# esp8266.net
KiCad netlist of a schematic drawn in EAGLE
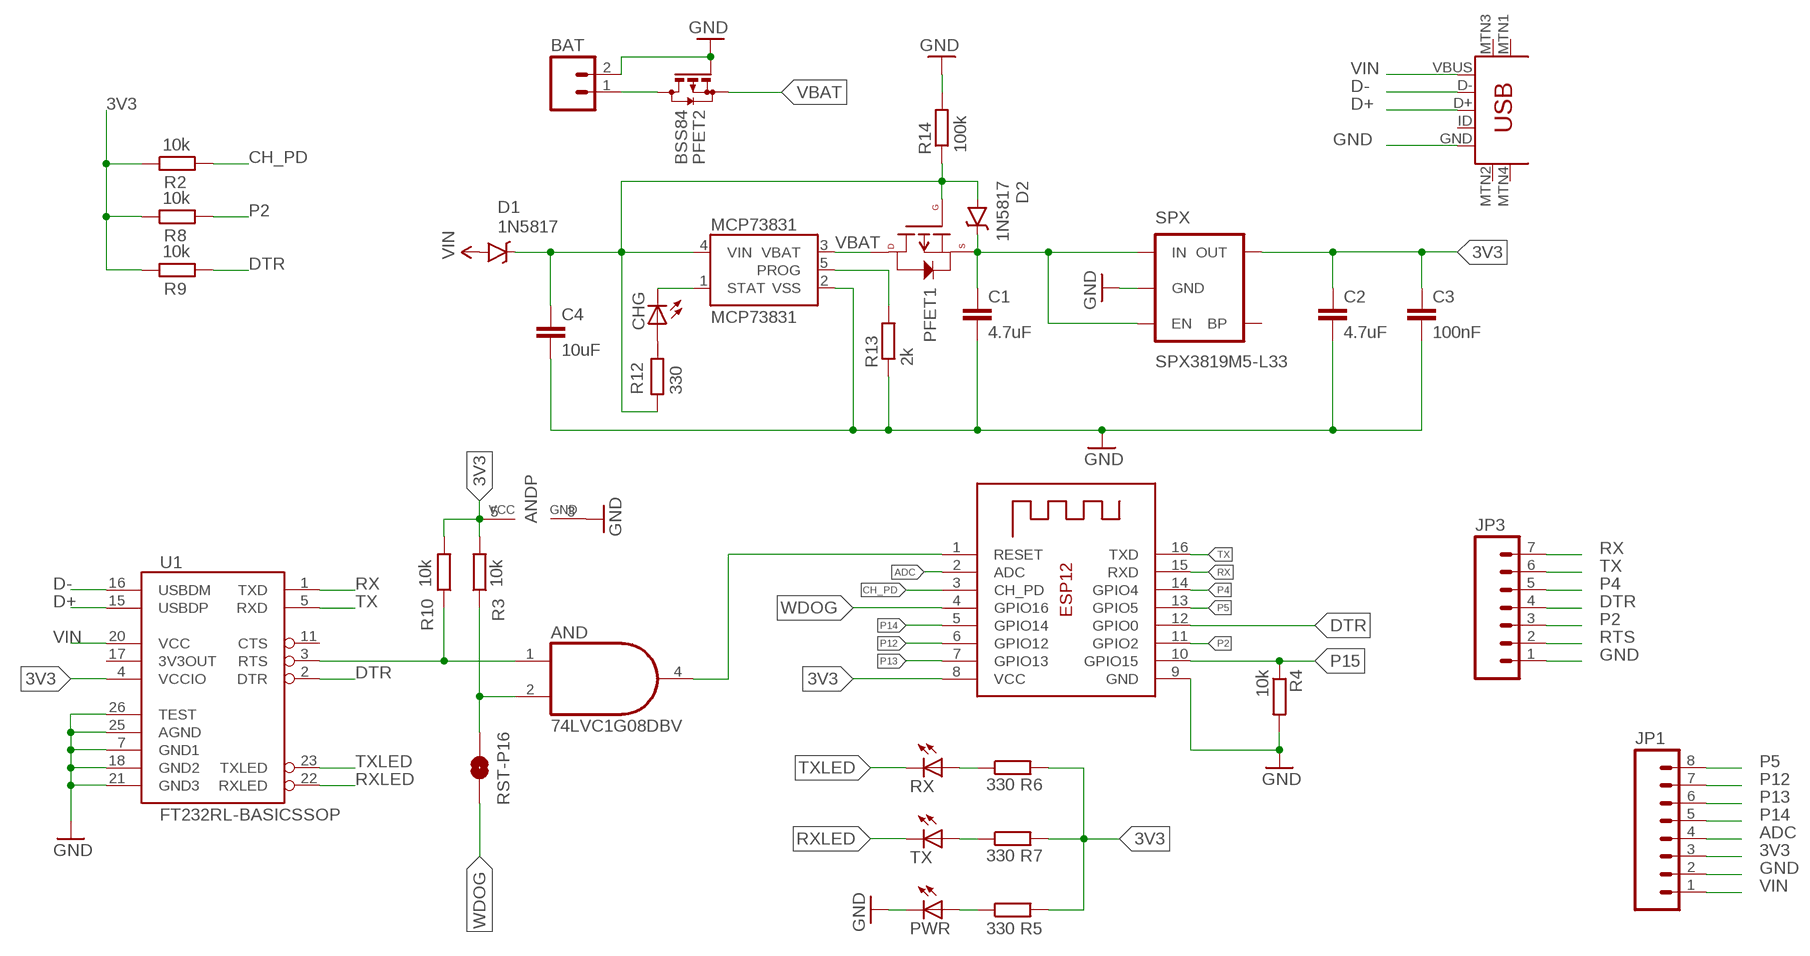
[diagram p0: schematic, sheet 1]

(export (version "E")
  (design (tool "Eeschema 10.0.6"))
  (components
    (comp (ref "AND")
      (value "74LVC1G08DBV")
      (footprint "eagle-import:SOT23-5")
      (libsource (lib "eagle-import") (part "741G08DBVLVC"))
    )
    (comp (ref "BAT")
      (value "M02LOCK")
      (footprint "eagle-import:1X02_LOCK")
      (libsource (lib "eagle-import") (part "M02LOCK"))
    )
    (comp (ref "C1")
      (value "4.7uF")
      (footprint "eagle-import:C0805")
      (libsource (lib "eagle-import") (part "C-EUC0805"))
    )
    (comp (ref "C2")
      (value "4.7uF")
      (footprint "eagle-import:C0805")
      (libsource (lib "eagle-import") (part "C-EUC0805"))
    )
    (comp (ref "C3")
      (value "100nF")
      (footprint "eagle-import:C0805")
      (libsource (lib "eagle-import") (part "C-EUC0805"))
    )
    (comp (ref "C4")
      (value "10uF")
      (footprint "eagle-import:C0805")
      (libsource (lib "eagle-import") (part "C-EUC0805"))
    )
    (comp (ref "CHG")
      (value "LEDCHIPLED_0805")
      (footprint "eagle-import:CHIPLED_0805")
      (libsource (lib "eagle-import") (part "LEDCHIPLED_0805"))
    )
    (comp (ref "D1")
      (value "1N5817")
      (footprint "eagle-import:SMA-DIODE")
      (libsource (lib "eagle-import") (part "DIODE-SCHOTTKY-MBRA140"))
    )
    (comp (ref "D2")
      (value "1N5817")
      (footprint "eagle-import:SMA-DIODE")
      (libsource (lib "eagle-import") (part "DIODE-SCHOTTKY-MBRA140"))
    )
    (comp (ref "ESP8266-07/12")
      (value "ESP-12")
      (footprint "eagle-import:ESP-12")
      (libsource (lib "eagle-import") (part "ESP-12"))
    )
    (comp (ref "JP1")
      (value "M08LOCK")
      (footprint "eagle-import:1X08_LOCK")
      (libsource (lib "eagle-import") (part "M08LOCK"))
    )
    (comp (ref "JP3")
      (value "M07LOCK")
      (footprint "eagle-import:1X07_LOCK")
      (libsource (lib "eagle-import") (part "M07LOCK"))
    )
    (comp (ref "MCP73831")
      (value "MCP73831")
      (footprint "eagle-import:SOT23-5")
      (libsource (lib "eagle-import") (part "MCP73831"))
    )
    (comp (ref "MINIUSB")
      (value "USB-MINIB-5PIN")
      (footprint "eagle-import:USB-MINIB")
      (libsource (lib "eagle-import") (part "USB-MINIB-5PIN"))
    )
    (comp (ref "PFET1")
      (value "P-CHANNEL-MOSFET")
      (footprint "eagle-import:SOT23-3")
      (libsource (lib "eagle-import") (part "P-CHANNEL-MOSFET"))
    )
    (comp (ref "PFET2")
      (value "BSS84")
      (footprint "eagle-import:SOT23")
      (libsource (lib "eagle-import") (part "BSS84"))
    )
    (comp (ref "PWR")
      (value "LEDCHIPLED_0805")
      (footprint "eagle-import:CHIPLED_0805")
      (libsource (lib "eagle-import") (part "LEDCHIPLED_0805"))
    )
    (comp (ref "R2")
      (value "10k")
      (footprint "eagle-import:R0805")
      (libsource (lib "eagle-import") (part "R-EU_R0805"))
    )
    (comp (ref "R3")
      (value "10k")
      (footprint "eagle-import:R0805")
      (libsource (lib "eagle-import") (part "R-EU_R0805"))
    )
    (comp (ref "R4")
      (value "10k")
      (footprint "eagle-import:R0805")
      (libsource (lib "eagle-import") (part "R-EU_R0805"))
    )
    (comp (ref "R5")
      (value "330")
      (footprint "eagle-import:R0805")
      (libsource (lib "eagle-import") (part "R-EU_R0805"))
    )
    (comp (ref "R6")
      (value "330")
      (footprint "eagle-import:R0805")
      (libsource (lib "eagle-import") (part "R-EU_R0805"))
    )
    (comp (ref "R7")
      (value "330")
      (footprint "eagle-import:R0805")
      (libsource (lib "eagle-import") (part "R-EU_R0805"))
    )
    (comp (ref "R8")
      (value "10k")
      (footprint "eagle-import:R0805")
      (libsource (lib "eagle-import") (part "R-EU_R0805"))
    )
    (comp (ref "R9")
      (value "10k")
      (footprint "eagle-import:R0805")
      (libsource (lib "eagle-import") (part "R-EU_R0805"))
    )
    (comp (ref "R10")
      (value "10k")
      (footprint "eagle-import:R0805")
      (libsource (lib "eagle-import") (part "R-EU_R0805"))
    )
    (comp (ref "R12")
      (value "330")
      (footprint "eagle-import:R0805")
      (libsource (lib "eagle-import") (part "R-EU_R0805"))
    )
    (comp (ref "R13")
      (value "2k")
      (footprint "eagle-import:R0805")
      (libsource (lib "eagle-import") (part "R-EU_R0805"))
    )
    (comp (ref "R14")
      (value "100k")
      (footprint "eagle-import:R0805")
      (libsource (lib "eagle-import") (part "R-EU_R0805"))
    )
    (comp (ref "RST-P16")
      (value "SOLDERJUMPERNO")
      (footprint "eagle-import:SJ_2S-NO")
      (libsource (lib "eagle-import") (part "SOLDERJUMPERNO"))
    )
    (comp (ref "RX")
      (value "LEDCHIPLED_0805")
      (footprint "eagle-import:CHIPLED_0805")
      (libsource (lib "eagle-import") (part "LEDCHIPLED_0805"))
    )
    (comp (ref "SPX")
      (value "SPX3819M5-L33")
      (footprint "eagle-import:SOT23-5")
      (libsource (lib "eagle-import") (part "V_REG_LDOSMD"))
    )
    (comp (ref "TX")
      (value "LEDCHIPLED_0805")
      (footprint "eagle-import:CHIPLED_0805")
      (libsource (lib "eagle-import") (part "LEDCHIPLED_0805"))
    )
    (comp (ref "U1")
      (value "FT232RL-BASICSSOP")
      (footprint "eagle-import:SSOP28DB")
      (libsource (lib "eagle-import") (part "FT232RL-BASICSSOP"))
    )
  )
  (nets
    (net (code "1") (name "/D+") (class "Default")
      (node (ref "MINIUSB") (pin "D+") (pinfunction "D+_D+") (pintype "bidirectional"))
      (node (ref "U1") (pin "15") (pinfunction "USBDP_15") (pintype "bidirectional"))
    )
    (net (code "2") (name "/D-") (class "Default")
      (node (ref "MINIUSB") (pin "D-") (pinfunction "D-_D-") (pintype "bidirectional"))
      (node (ref "U1") (pin "16") (pinfunction "USBDM_16") (pintype "bidirectional"))
    )
    (net (code "3") (name "/RTS") (class "Default")
      (node (ref "AND") (pin "4") (pinfunction "O_4") (pintype "output"))
      (node (ref "ESP8266-07/12") (pin "1") (pinfunction "RESET_1") (pintype "input"))
      (node (ref "JP3") (pin "2") (pinfunction "2_2") (pintype "passive"))
    )
    (net (code "4") (name "3V3") (class "Default")
      (node (ref "AND") (pin "5") (pinfunction "VCC_5") (pintype "power_in"))
      (node (ref "C2") (pin "1") (pinfunction "1_1") (pintype "passive"))
      (node (ref "C3") (pin "1") (pinfunction "1_1") (pintype "passive"))
      (node (ref "ESP8266-07/12") (pin "8") (pinfunction "VCC_8") (pintype "power_in"))
      (node (ref "JP1") (pin "3") (pinfunction "3_3") (pintype "passive"))
      (node (ref "R10") (pin "2") (pinfunction "2_2") (pintype "passive"))
      (node (ref "R2") (pin "1") (pinfunction "1_1") (pintype "passive"))
      (node (ref "R3") (pin "2") (pinfunction "2_2") (pintype "passive"))
      (node (ref "R5") (pin "2") (pinfunction "2_2") (pintype "passive"))
      (node (ref "R6") (pin "2") (pinfunction "2_2") (pintype "passive"))
      (node (ref "R7") (pin "2") (pinfunction "2_2") (pintype "passive"))
      (node (ref "R8") (pin "1") (pinfunction "1_1") (pintype "passive"))
      (node (ref "R9") (pin "1") (pinfunction "1_1") (pintype "passive"))
      (node (ref "SPX") (pin "5") (pinfunction "OUT_5") (pintype "passive"))
      (node (ref "U1") (pin "4") (pinfunction "VCCIO_4") (pintype "power_in"))
    )
    (net (code "5") (name "ADC") (class "Default")
      (node (ref "ESP8266-07/12") (pin "2") (pinfunction "ADC_2") (pintype "passive"))
      (node (ref "JP1") (pin "4") (pinfunction "4_4") (pintype "passive"))
    )
    (net (code "6") (name "CH_PD") (class "Default")
      (node (ref "ESP8266-07/12") (pin "3") (pinfunction "CH_PD_3") (pintype "input"))
      (node (ref "R2") (pin "2") (pinfunction "2_2") (pintype "passive"))
    )
    (net (code "7") (name "DTR") (class "Default")
      (node (ref "ESP8266-07/12") (pin "12") (pinfunction "GPIO0_12") (pintype "bidirectional"))
      (node (ref "JP3") (pin "4") (pinfunction "4_4") (pintype "passive"))
      (node (ref "R9") (pin "2") (pinfunction "2_2") (pintype "passive"))
      (node (ref "U1") (pin "2") (pinfunction "DTR_2") (pintype "bidirectional"))
    )
    (net (code "8") (name "GND") (class "Default")
      (node (ref "AND") (pin "3") (pinfunction "GND_3") (pintype "power_in"))
      (node (ref "BAT") (pin "2") (pinfunction "2_2") (pintype "passive"))
      (node (ref "C1") (pin "2") (pinfunction "2_2") (pintype "passive"))
      (node (ref "C2") (pin "2") (pinfunction "2_2") (pintype "passive"))
      (node (ref "C3") (pin "2") (pinfunction "2_2") (pintype "passive"))
      (node (ref "C4") (pin "2") (pinfunction "2_2") (pintype "passive"))
      (node (ref "ESP8266-07/12") (pin "9") (pinfunction "GND_9") (pintype "power_in"))
      (node (ref "JP1") (pin "2") (pinfunction "2_2") (pintype "passive"))
      (node (ref "JP3") (pin "1") (pinfunction "1_1") (pintype "passive"))
      (node (ref "MCP73831") (pin "2") (pinfunction "VSS_2") (pintype "power_in"))
      (node (ref "MINIUSB") (pin "GND") (pinfunction "GND_GND") (pintype "bidirectional"))
      (node (ref "PFET2") (pin "1") (pinfunction "G_1") (pintype "passive"))
      (node (ref "PWR") (pin "C") (pinfunction "C_C") (pintype "passive"))
      (node (ref "R13") (pin "1") (pinfunction "1_1") (pintype "passive"))
      (node (ref "R14") (pin "2") (pinfunction "2_2") (pintype "passive"))
      (node (ref "R4") (pin "2") (pinfunction "2_2") (pintype "passive"))
      (node (ref "SPX") (pin "2") (pinfunction "GND_2") (pintype "input"))
      (node (ref "U1") (pin "18") (pinfunction "GND2_18") (pintype "power_in"))
      (node (ref "U1") (pin "21") (pinfunction "GND3_21") (pintype "power_in"))
      (node (ref "U1") (pin "25") (pinfunction "AGND_25") (pintype "power_in"))
      (node (ref "U1") (pin "26") (pinfunction "TEST_26") (pintype "input"))
      (node (ref "U1") (pin "7") (pinfunction "GND1_7") (pintype "power_in"))
    )
    (net (code "9") (name "Net-(ANDA-I0)") (class "Default")
      (node (ref "AND") (pin "1") (pinfunction "I0_1") (pintype "input"))
      (node (ref "R10") (pin "1") (pinfunction "1_1") (pintype "passive"))
      (node (ref "U1") (pin "3") (pinfunction "RTS_3") (pintype "bidirectional"))
    )
    (net (code "10") (name "Net-(ANDA-I1)") (class "Default")
      (node (ref "AND") (pin "2") (pinfunction "I1_2") (pintype "input"))
      (node (ref "R3") (pin "1") (pinfunction "1_1") (pintype "passive"))
      (node (ref "RST-P16") (pin "1") (pinfunction "1_1") (pintype "passive"))
    )
    (net (code "11") (name "Net-(CHG-PadA)") (class "Default")
      (node (ref "CHG") (pin "A") (pinfunction "A_A") (pintype "passive"))
      (node (ref "R12") (pin "2") (pinfunction "2_2") (pintype "passive"))
    )
    (net (code "12") (name "Net-(MCP73831-PROG)") (class "Default")
      (node (ref "MCP73831") (pin "5") (pinfunction "PROG_5") (pintype "input"))
      (node (ref "R13") (pin "2") (pinfunction "2_2") (pintype "passive"))
    )
    (net (code "13") (name "Net-(MCP73831-STAT)") (class "Default")
      (node (ref "CHG") (pin "C") (pinfunction "C_C") (pintype "passive"))
      (node (ref "MCP73831") (pin "1") (pinfunction "STAT_1") (pintype "output"))
    )
    (net (code "14") (name "Net-(MCP73831-VIN)") (class "Default")
      (node (ref "C4") (pin "1") (pinfunction "1_1") (pintype "passive"))
      (node (ref "D1") (pin "C") (pinfunction "C_C") (pintype "passive"))
      (node (ref "D2") (pin "A") (pinfunction "A_A") (pintype "passive"))
      (node (ref "MCP73831") (pin "4") (pinfunction "VIN_4") (pintype "power_in"))
      (node (ref "PFET1") (pin "1") (pinfunction "G_1") (pintype "passive"))
      (node (ref "R12") (pin "1") (pinfunction "1_1") (pintype "passive"))
      (node (ref "R14") (pin "1") (pinfunction "1_1") (pintype "passive"))
    )
    (net (code "15") (name "Net-(PFET1-S)") (class "Default")
      (node (ref "C1") (pin "1") (pinfunction "1_1") (pintype "passive"))
      (node (ref "D2") (pin "C") (pinfunction "C_C") (pintype "passive"))
      (node (ref "PFET1") (pin "2") (pinfunction "S_2") (pintype "passive"))
      (node (ref "SPX") (pin "1") (pinfunction "IN_1") (pintype "input"))
      (node (ref "SPX") (pin "3") (pinfunction "EN_3") (pintype "input"))
    )
    (net (code "16") (name "Net-(PFET2-D)") (class "Default")
      (node (ref "BAT") (pin "1") (pinfunction "1_1") (pintype "passive"))
      (node (ref "PFET2") (pin "3") (pinfunction "D_3") (pintype "passive"))
    )
    (net (code "17") (name "Net-(PWR-PadA)") (class "Default")
      (node (ref "PWR") (pin "A") (pinfunction "A_A") (pintype "passive"))
      (node (ref "R5") (pin "1") (pinfunction "1_1") (pintype "passive"))
    )
    (net (code "18") (name "Net-(R6-Pad1)") (class "Default")
      (node (ref "R6") (pin "1") (pinfunction "1_1") (pintype "passive"))
      (node (ref "RX") (pin "A") (pinfunction "A_A") (pintype "passive"))
    )
    (net (code "19") (name "Net-(R7-Pad1)") (class "Default")
      (node (ref "R7") (pin "1") (pinfunction "1_1") (pintype "passive"))
      (node (ref "TX") (pin "A") (pinfunction "A_A") (pintype "passive"))
    )
    (net (code "20") (name "P2") (class "Default")
      (node (ref "ESP8266-07/12") (pin "11") (pinfunction "GPIO2_11") (pintype "bidirectional"))
      (node (ref "JP3") (pin "3") (pinfunction "3_3") (pintype "passive"))
      (node (ref "R8") (pin "2") (pinfunction "2_2") (pintype "passive"))
    )
    (net (code "21") (name "P4") (class "Default")
      (node (ref "ESP8266-07/12") (pin "14") (pinfunction "GPIO4_14") (pintype "bidirectional"))
      (node (ref "JP3") (pin "5") (pinfunction "5_5") (pintype "passive"))
    )
    (net (code "22") (name "P5") (class "Default")
      (node (ref "ESP8266-07/12") (pin "13") (pinfunction "GPIO5_13") (pintype "bidirectional"))
      (node (ref "JP1") (pin "8") (pinfunction "8_8") (pintype "passive"))
    )
    (net (code "23") (name "P12") (class "Default")
      (node (ref "ESP8266-07/12") (pin "6") (pinfunction "GPIO12_6") (pintype "bidirectional"))
      (node (ref "JP1") (pin "7") (pinfunction "7_7") (pintype "passive"))
    )
    (net (code "24") (name "P13") (class "Default")
      (node (ref "ESP8266-07/12") (pin "7") (pinfunction "GPIO13_7") (pintype "bidirectional"))
      (node (ref "JP1") (pin "6") (pinfunction "6_6") (pintype "passive"))
    )
    (net (code "25") (name "P14") (class "Default")
      (node (ref "ESP8266-07/12") (pin "5") (pinfunction "GPIO14_5") (pintype "bidirectional"))
      (node (ref "JP1") (pin "5") (pinfunction "5_5") (pintype "passive"))
    )
    (net (code "26") (name "P15") (class "Default")
      (node (ref "ESP8266-07/12") (pin "10") (pinfunction "GPIO15_10") (pintype "bidirectional"))
      (node (ref "R4") (pin "1") (pinfunction "1_1") (pintype "passive"))
    )
    (net (code "27") (name "RX") (class "Default")
      (node (ref "ESP8266-07/12") (pin "15") (pinfunction "RXD_15") (pintype "input"))
      (node (ref "JP3") (pin "7") (pinfunction "7_7") (pintype "passive"))
      (node (ref "U1") (pin "1") (pinfunction "TXD_1") (pintype "output"))
    )
    (net (code "28") (name "RXLED") (class "Default")
      (node (ref "TX") (pin "C") (pinfunction "C_C") (pintype "passive"))
      (node (ref "U1") (pin "22") (pinfunction "RXLED_22") (pintype "bidirectional"))
    )
    (net (code "29") (name "TX") (class "Default")
      (node (ref "ESP8266-07/12") (pin "16") (pinfunction "TXD_16") (pintype "output"))
      (node (ref "JP3") (pin "6") (pinfunction "6_6") (pintype "passive"))
      (node (ref "U1") (pin "5") (pinfunction "RXD_5") (pintype "input"))
    )
    (net (code "30") (name "TXLED") (class "Default")
      (node (ref "RX") (pin "C") (pinfunction "C_C") (pintype "passive"))
      (node (ref "U1") (pin "23") (pinfunction "TXLED_23") (pintype "bidirectional"))
    )
    (net (code "31") (name "VBAT") (class "Default")
      (node (ref "MCP73831") (pin "3") (pinfunction "VBAT_3") (pintype "power_in"))
      (node (ref "PFET1") (pin "3") (pinfunction "D_3") (pintype "passive"))
      (node (ref "PFET2") (pin "2") (pinfunction "S_2") (pintype "passive"))
    )
    (net (code "32") (name "VIN") (class "Default")
      (node (ref "D1") (pin "A") (pinfunction "A_A") (pintype "passive"))
      (node (ref "JP1") (pin "1") (pinfunction "1_1") (pintype "passive"))
      (node (ref "MINIUSB") (pin "VBUS") (pinfunction "VBUS_VBUS") (pintype "bidirectional"))
      (node (ref "U1") (pin "20") (pinfunction "VCC_20") (pintype "power_in"))
    )
    (net (code "33") (name "WDOG") (class "Default")
      (node (ref "ESP8266-07/12") (pin "4") (pinfunction "GPIO16_4") (pintype "bidirectional"))
      (node (ref "RST-P16") (pin "2") (pinfunction "2_2") (pintype "passive"))
    )
    (net (code "34") (name "unconnected-(MINIUSB-MTN1-PadMTN3)") (class "Default")
      (node (ref "MINIUSB") (pin "MTN3") (pinfunction "MTN1_MTN3") (pintype "bidirectional"))
    )
    (net (code "35") (name "unconnected-(MINIUSB-MTN2-PadMTN1)") (class "Default")
      (node (ref "MINIUSB") (pin "MTN1") (pinfunction "MTN2_MTN1") (pintype "bidirectional"))
    )
    (net (code "36") (name "unconnected-(MINIUSB-MTN3-PadMTN2)") (class "Default")
      (node (ref "MINIUSB") (pin "MTN2") (pinfunction "MTN3_MTN2") (pintype "bidirectional"))
    )
    (net (code "37") (name "unconnected-(MINIUSB-PadID)") (class "Default")
      (node (ref "MINIUSB") (pin "ID") (pinfunction "ID_ID") (pintype "bidirectional"))
    )
    (net (code "38") (name "unconnected-(MINIUSB-PadMTN4)") (class "Default")
      (node (ref "MINIUSB") (pin "MTN4") (pinfunction "MTN4_MTN4") (pintype "bidirectional"))
    )
    (net (code "39") (name "unconnected-(SPX-BP-Pad4)") (class "Default")
      (node (ref "SPX") (pin "4") (pinfunction "BP_4") (pintype "input"))
    )
    (net (code "40") (name "unconnected-(U1-3V3OUT-Pad17)") (class "Default")
      (node (ref "U1") (pin "17") (pinfunction "3V3OUT_17") (pintype "output"))
    )
    (net (code "41") (name "unconnected-(U1-CTS-Pad11)") (class "Default")
      (node (ref "U1") (pin "11") (pinfunction "CTS_11") (pintype "bidirectional"))
    )
  )
)
